# Sheet1.net
KiCad netlist of a schematic drawn in Altium Designer
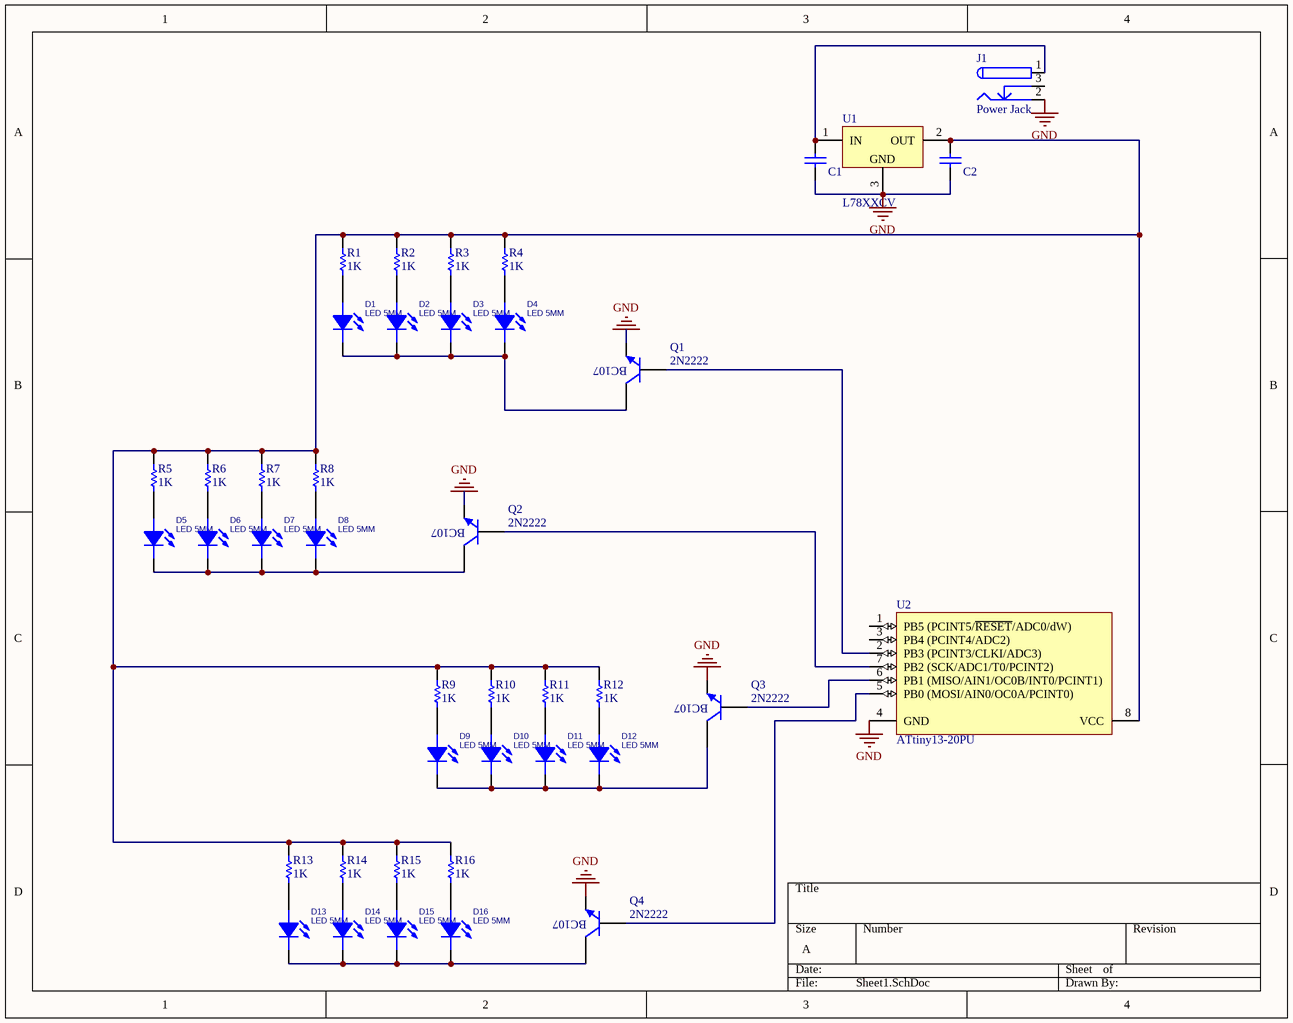
[diagram p0: Sheet1.SchDoc]

(export (version "E")
  (design (tool "Eeschema 10.0.6"))
  (components
    (comp (ref "C1")
      (value "~")
      (footprint "CBB22")
      (description "Polypropylene film with epoxy Cap CBB22 105J400V")
      (fields (field (name "MANUFACTURER") "CHINA") (field (name "DESIGNER") "Abbas Basereh"))
      (libsource (lib "Altium") (part "Cap CBB22 105J400V"))
    )
    (comp (ref "C2")
      (value "~")
      (footprint "CBB22")
      (description "Polypropylene film with epoxy Cap CBB22 105J400V")
      (fields (field (name "MANUFACTURER") "CHINA") (field (name "DESIGNER") "Abbas Basereh"))
      (libsource (lib "Altium") (part "Cap CBB22 105J400V"))
    )
    (comp (ref "D1")
      (value "LED 5MM")
      (footprint "LED5MM_BLUE")
      (description "Light Emitting Diode")
      (fields (field (name "DESIGNER") "Abbas Basereh"))
      (libsource (lib "Altium") (part "LED 5MM"))
    )
    (comp (ref "D2")
      (value "LED 5MM")
      (footprint "LED5MM_BLUE")
      (description "Light Emitting Diode")
      (fields (field (name "DESIGNER") "Abbas Basereh"))
      (libsource (lib "Altium") (part "LED 5MM"))
    )
    (comp (ref "D3")
      (value "LED 5MM")
      (footprint "LED5MM_BLUE")
      (description "Light Emitting Diode")
      (fields (field (name "DESIGNER") "Abbas Basereh"))
      (libsource (lib "Altium") (part "LED 5MM"))
    )
    (comp (ref "D4")
      (value "LED 5MM")
      (footprint "LED5MM_BLUE")
      (description "Light Emitting Diode")
      (fields (field (name "DESIGNER") "Abbas Basereh"))
      (libsource (lib "Altium") (part "LED 5MM"))
    )
    (comp (ref "D5")
      (value "LED 5MM")
      (footprint "LED5MM_BLUE")
      (description "Light Emitting Diode")
      (fields (field (name "DESIGNER") "Abbas Basereh"))
      (libsource (lib "Altium") (part "LED 5MM"))
    )
    (comp (ref "D6")
      (value "LED 5MM")
      (footprint "LED5MM_BLUE")
      (description "Light Emitting Diode")
      (fields (field (name "DESIGNER") "Abbas Basereh"))
      (libsource (lib "Altium") (part "LED 5MM"))
    )
    (comp (ref "D7")
      (value "LED 5MM")
      (footprint "LED5MM_BLUE")
      (description "Light Emitting Diode")
      (fields (field (name "DESIGNER") "Abbas Basereh"))
      (libsource (lib "Altium") (part "LED 5MM"))
    )
    (comp (ref "D8")
      (value "LED 5MM")
      (footprint "LED5MM_BLUE")
      (description "Light Emitting Diode")
      (fields (field (name "DESIGNER") "Abbas Basereh"))
      (libsource (lib "Altium") (part "LED 5MM"))
    )
    (comp (ref "D9")
      (value "LED 5MM")
      (footprint "LED5MM_BLUE")
      (description "Light Emitting Diode")
      (fields (field (name "DESIGNER") "Abbas Basereh"))
      (libsource (lib "Altium") (part "LED 5MM"))
    )
    (comp (ref "D10")
      (value "LED 5MM")
      (footprint "LED5MM_BLUE")
      (description "Light Emitting Diode")
      (fields (field (name "DESIGNER") "Abbas Basereh"))
      (libsource (lib "Altium") (part "LED 5MM"))
    )
    (comp (ref "D11")
      (value "LED 5MM")
      (footprint "LED5MM_BLUE")
      (description "Light Emitting Diode")
      (fields (field (name "DESIGNER") "Abbas Basereh"))
      (libsource (lib "Altium") (part "LED 5MM"))
    )
    (comp (ref "D12")
      (value "LED 5MM")
      (footprint "LED5MM_BLUE")
      (description "Light Emitting Diode")
      (fields (field (name "DESIGNER") "Abbas Basereh"))
      (libsource (lib "Altium") (part "LED 5MM"))
    )
    (comp (ref "D13")
      (value "LED 5MM")
      (footprint "LED5MM_BLUE")
      (description "Light Emitting Diode")
      (fields (field (name "DESIGNER") "Abbas Basereh"))
      (libsource (lib "Altium") (part "LED 5MM"))
    )
    (comp (ref "D14")
      (value "LED 5MM")
      (footprint "LED5MM_BLUE")
      (description "Light Emitting Diode")
      (fields (field (name "DESIGNER") "Abbas Basereh"))
      (libsource (lib "Altium") (part "LED 5MM"))
    )
    (comp (ref "D15")
      (value "LED 5MM")
      (footprint "LED5MM_BLUE")
      (description "Light Emitting Diode")
      (fields (field (name "DESIGNER") "Abbas Basereh"))
      (libsource (lib "Altium") (part "LED 5MM"))
    )
    (comp (ref "D16")
      (value "LED 5MM")
      (footprint "LED5MM_BLUE")
      (description "Light Emitting Diode")
      (fields (field (name "DESIGNER") "Abbas Basereh"))
      (libsource (lib "Altium") (part "LED 5MM"))
    )
    (comp (ref "J1")
      (value "Power Jack")
      (footprint "Power Jack")
      (fields (field (name "DESIGNER") "Saeid Jorablo"))
      (libsource (lib "My_Library") (part "Power Jack"))
    )
    (comp (ref "Q1")
      (value "2N2222")
      (footprint "2N2222")
      (description "NPN Transistor")
      (libsource (lib "Altium") (part "2N2222"))
    )
    (comp (ref "Q2")
      (value "2N2222")
      (footprint "2N2222")
      (description "NPN Transistor")
      (libsource (lib "Altium") (part "2N2222"))
    )
    (comp (ref "Q3")
      (value "2N2222")
      (footprint "2N2222")
      (description "NPN Transistor")
      (libsource (lib "Altium") (part "2N2222"))
    )
    (comp (ref "Q4")
      (value "2N2222")
      (footprint "2N2222")
      (description "NPN Transistor")
      (libsource (lib "Altium") (part "2N2222"))
    )
    (comp (ref "R1")
      (value "1K")
      (footprint "RES-(1/1)")
      (description "TOTAL DIP RESISTOR PACK")
      (fields (field (name "DESIGNER") "Ali Hafizi"))
      (libsource (lib "Altium") (part "RES DIP PACKAGE"))
    )
    (comp (ref "R2")
      (value "1K")
      (footprint "RES-(1/1)")
      (description "TOTAL DIP RESISTOR PACK")
      (fields (field (name "DESIGNER") "Ali Hafizi"))
      (libsource (lib "Altium") (part "RES DIP PACKAGE"))
    )
    (comp (ref "R3")
      (value "1K")
      (footprint "RES-(1/1)")
      (description "TOTAL DIP RESISTOR PACK")
      (fields (field (name "DESIGNER") "Ali Hafizi"))
      (libsource (lib "Altium") (part "RES DIP PACKAGE"))
    )
    (comp (ref "R4")
      (value "1K")
      (footprint "RES-(1/1)")
      (description "TOTAL DIP RESISTOR PACK")
      (fields (field (name "DESIGNER") "Ali Hafizi"))
      (libsource (lib "Altium") (part "RES DIP PACKAGE"))
    )
    (comp (ref "R5")
      (value "1K")
      (footprint "RES-(1/1)")
      (description "TOTAL DIP RESISTOR PACK")
      (fields (field (name "DESIGNER") "Ali Hafizi"))
      (libsource (lib "Altium") (part "RES DIP PACKAGE"))
    )
    (comp (ref "R6")
      (value "1K")
      (footprint "RES-(1/1)")
      (description "TOTAL DIP RESISTOR PACK")
      (fields (field (name "DESIGNER") "Ali Hafizi"))
      (libsource (lib "Altium") (part "RES DIP PACKAGE"))
    )
    (comp (ref "R7")
      (value "1K")
      (footprint "RES-(1/1)")
      (description "TOTAL DIP RESISTOR PACK")
      (fields (field (name "DESIGNER") "Ali Hafizi"))
      (libsource (lib "Altium") (part "RES DIP PACKAGE"))
    )
    (comp (ref "R8")
      (value "1K")
      (footprint "RES-(1/1)")
      (description "TOTAL DIP RESISTOR PACK")
      (fields (field (name "DESIGNER") "Ali Hafizi"))
      (libsource (lib "Altium") (part "RES DIP PACKAGE"))
    )
    (comp (ref "R9")
      (value "1K")
      (footprint "RES-(1/1)")
      (description "TOTAL DIP RESISTOR PACK")
      (fields (field (name "DESIGNER") "Ali Hafizi"))
      (libsource (lib "Altium") (part "RES DIP PACKAGE"))
    )
    (comp (ref "R10")
      (value "1K")
      (footprint "RES-(1/1)")
      (description "TOTAL DIP RESISTOR PACK")
      (fields (field (name "DESIGNER") "Ali Hafizi"))
      (libsource (lib "Altium") (part "RES DIP PACKAGE"))
    )
    (comp (ref "R11")
      (value "1K")
      (footprint "RES-(1/1)")
      (description "TOTAL DIP RESISTOR PACK")
      (fields (field (name "DESIGNER") "Ali Hafizi"))
      (libsource (lib "Altium") (part "RES DIP PACKAGE"))
    )
    (comp (ref "R12")
      (value "1K")
      (footprint "RES-(1/1)")
      (description "TOTAL DIP RESISTOR PACK")
      (fields (field (name "DESIGNER") "Ali Hafizi"))
      (libsource (lib "Altium") (part "RES DIP PACKAGE"))
    )
    (comp (ref "R13")
      (value "1K")
      (footprint "RES-(1/1)")
      (description "TOTAL DIP RESISTOR PACK")
      (fields (field (name "DESIGNER") "Ali Hafizi"))
      (libsource (lib "Altium") (part "RES DIP PACKAGE"))
    )
    (comp (ref "R14")
      (value "1K")
      (footprint "RES-(1/1)")
      (description "TOTAL DIP RESISTOR PACK")
      (fields (field (name "DESIGNER") "Ali Hafizi"))
      (libsource (lib "Altium") (part "RES DIP PACKAGE"))
    )
    (comp (ref "R15")
      (value "1K")
      (footprint "RES-(1/1)")
      (description "TOTAL DIP RESISTOR PACK")
      (fields (field (name "DESIGNER") "Ali Hafizi"))
      (libsource (lib "Altium") (part "RES DIP PACKAGE"))
    )
    (comp (ref "R16")
      (value "1K")
      (footprint "RES-(1/1)")
      (description "TOTAL DIP RESISTOR PACK")
      (fields (field (name "DESIGNER") "Ali Hafizi"))
      (libsource (lib "Altium") (part "RES DIP PACKAGE"))
    )
    (comp (ref "U1")
      (value "L78XXCV")
      (footprint "78XXCV - Right")
      (description "Fixed Voltage Regulator")
      (fields (field (name "DESIGNER") "Saeid Jorablo"))
      (libsource (lib "Altium") (part "L78XXCV"))
    )
    (comp (ref "U2")
      (value "ATtiny13-20PU")
      (footprint "8P3")
      (fields (field (name "PUBLISHER") "Abbas Basereh"))
      (libsource (lib "Altium") (part "ATtiny13-20PU"))
    )
  )
  (nets
    (net (code "1") (name "GND") (class "Default")
      (node (ref "C1") (pin "1") (pinfunction "1_1") (pintype "passive"))
      (node (ref "C2") (pin "1") (pinfunction "1_1") (pintype "passive"))
      (node (ref "J1") (pin "2") (pinfunction "2_2") (pintype "power_in"))
      (node (ref "Q1") (pin "1") (pinfunction "E_1") (pintype "passive"))
      (node (ref "Q2") (pin "1") (pinfunction "E_1") (pintype "passive"))
      (node (ref "U1") (pin "3") (pinfunction "GND_3") (pintype "passive"))
      (node (ref "U2") (pin "4") (pinfunction "GND_4") (pintype "power_in"))
    )
    (net (code "2") (name "Net-(D1-ANODE)") (class "Default")
      (node (ref "D1") (pin "1") (pinfunction "ANODE_1") (pintype "passive"))
      (node (ref "R1") (pin "1") (pinfunction "1_1") (pintype "passive"))
    )
    (net (code "3") (name "Net-(D1-CATHODE)") (class "Default")
      (node (ref "D1") (pin "2") (pinfunction "CATHODE_2") (pintype "passive"))
      (node (ref "D2") (pin "2") (pinfunction "CATHODE_2") (pintype "passive"))
      (node (ref "D3") (pin "2") (pinfunction "CATHODE_2") (pintype "passive"))
      (node (ref "D4") (pin "2") (pinfunction "CATHODE_2") (pintype "passive"))
      (node (ref "Q1") (pin "3") (pinfunction "C_3") (pintype "passive"))
    )
    (net (code "4") (name "Net-(D2-ANODE)") (class "Default")
      (node (ref "D2") (pin "1") (pinfunction "ANODE_1") (pintype "passive"))
      (node (ref "R2") (pin "1") (pinfunction "1_1") (pintype "passive"))
    )
    (net (code "5") (name "Net-(D3-ANODE)") (class "Default")
      (node (ref "D3") (pin "1") (pinfunction "ANODE_1") (pintype "passive"))
      (node (ref "R3") (pin "1") (pinfunction "1_1") (pintype "passive"))
    )
    (net (code "6") (name "Net-(D4-ANODE)") (class "Default")
      (node (ref "D4") (pin "1") (pinfunction "ANODE_1") (pintype "passive"))
      (node (ref "R4") (pin "1") (pinfunction "1_1") (pintype "passive"))
    )
    (net (code "7") (name "Net-(D5-ANODE)") (class "Default")
      (node (ref "D5") (pin "1") (pinfunction "ANODE_1") (pintype "passive"))
      (node (ref "R5") (pin "1") (pinfunction "1_1") (pintype "passive"))
    )
    (net (code "8") (name "Net-(D5-CATHODE)") (class "Default")
      (node (ref "D5") (pin "2") (pinfunction "CATHODE_2") (pintype "passive"))
      (node (ref "D6") (pin "2") (pinfunction "CATHODE_2") (pintype "passive"))
      (node (ref "D7") (pin "2") (pinfunction "CATHODE_2") (pintype "passive"))
      (node (ref "D8") (pin "2") (pinfunction "CATHODE_2") (pintype "passive"))
      (node (ref "Q2") (pin "3") (pinfunction "C_3") (pintype "passive"))
    )
    (net (code "9") (name "Net-(D6-ANODE)") (class "Default")
      (node (ref "D6") (pin "1") (pinfunction "ANODE_1") (pintype "passive"))
      (node (ref "R6") (pin "1") (pinfunction "1_1") (pintype "passive"))
    )
    (net (code "10") (name "Net-(D7-ANODE)") (class "Default")
      (node (ref "D7") (pin "1") (pinfunction "ANODE_1") (pintype "passive"))
      (node (ref "R7") (pin "1") (pinfunction "1_1") (pintype "passive"))
    )
    (net (code "11") (name "Net-(D8-ANODE)") (class "Default")
      (node (ref "D8") (pin "1") (pinfunction "ANODE_1") (pintype "passive"))
      (node (ref "R8") (pin "1") (pinfunction "1_1") (pintype "passive"))
    )
    (net (code "12") (name "Net-(D9-ANODE)") (class "Default")
      (node (ref "D9") (pin "1") (pinfunction "ANODE_1") (pintype "passive"))
      (node (ref "R9") (pin "1") (pinfunction "1_1") (pintype "passive"))
    )
    (net (code "13") (name "Net-(D10-ANODE)") (class "Default")
      (node (ref "D10") (pin "1") (pinfunction "ANODE_1") (pintype "passive"))
      (node (ref "R10") (pin "1") (pinfunction "1_1") (pintype "passive"))
    )
    (net (code "14") (name "Net-(D10-CATHODE)") (class "Default")
      (node (ref "D10") (pin "2") (pinfunction "CATHODE_2") (pintype "passive"))
      (node (ref "D11") (pin "2") (pinfunction "CATHODE_2") (pintype "passive"))
      (node (ref "D12") (pin "2") (pinfunction "CATHODE_2") (pintype "passive"))
      (node (ref "D9") (pin "2") (pinfunction "CATHODE_2") (pintype "passive"))
      (node (ref "Q3") (pin "3") (pinfunction "C_3") (pintype "passive"))
    )
    (net (code "15") (name "Net-(D11-ANODE)") (class "Default")
      (node (ref "D11") (pin "1") (pinfunction "ANODE_1") (pintype "passive"))
      (node (ref "R11") (pin "1") (pinfunction "1_1") (pintype "passive"))
    )
    (net (code "16") (name "Net-(D12-ANODE)") (class "Default")
      (node (ref "D12") (pin "1") (pinfunction "ANODE_1") (pintype "passive"))
      (node (ref "R12") (pin "1") (pinfunction "1_1") (pintype "passive"))
    )
    (net (code "17") (name "Net-(D13-ANODE)") (class "Default")
      (node (ref "D13") (pin "1") (pinfunction "ANODE_1") (pintype "passive"))
      (node (ref "R13") (pin "1") (pinfunction "1_1") (pintype "passive"))
    )
    (net (code "18") (name "Net-(D13-CATHODE)") (class "Default")
      (node (ref "D13") (pin "2") (pinfunction "CATHODE_2") (pintype "passive"))
      (node (ref "D14") (pin "2") (pinfunction "CATHODE_2") (pintype "passive"))
      (node (ref "D15") (pin "2") (pinfunction "CATHODE_2") (pintype "passive"))
      (node (ref "D16") (pin "2") (pinfunction "CATHODE_2") (pintype "passive"))
      (node (ref "Q4") (pin "3") (pinfunction "C_3") (pintype "passive"))
    )
    (net (code "19") (name "Net-(D14-ANODE)") (class "Default")
      (node (ref "D14") (pin "1") (pinfunction "ANODE_1") (pintype "passive"))
      (node (ref "R14") (pin "1") (pinfunction "1_1") (pintype "passive"))
    )
    (net (code "20") (name "Net-(D15-ANODE)") (class "Default")
      (node (ref "D15") (pin "1") (pinfunction "ANODE_1") (pintype "passive"))
      (node (ref "R15") (pin "1") (pinfunction "1_1") (pintype "passive"))
    )
    (net (code "21") (name "Net-(D16-ANODE)") (class "Default")
      (node (ref "D16") (pin "1") (pinfunction "ANODE_1") (pintype "passive"))
      (node (ref "R16") (pin "1") (pinfunction "1_1") (pintype "passive"))
    )
    (net (code "22") (name "Net-(Q1-B)") (class "Default")
      (node (ref "Q1") (pin "2") (pinfunction "B_2") (pintype "passive"))
      (node (ref "U2") (pin "2") (pinfunction "PB3_(PCINT3/CLKI/ADC3)_2") (pintype "bidirectional"))
    )
    (net (code "23") (name "Net-(Q2-B)") (class "Default")
      (node (ref "Q2") (pin "2") (pinfunction "B_2") (pintype "passive"))
      (node (ref "U2") (pin "7") (pinfunction "PB2_(SCK/ADC1/T0/PCINT2)_7") (pintype "bidirectional"))
    )
    (net (code "24") (name "Net-(Q3-B)") (class "Default")
      (node (ref "Q3") (pin "2") (pinfunction "B_2") (pintype "passive"))
      (node (ref "U2") (pin "6") (pinfunction "PB1_(MISO/AIN1/OC0B/INT0/PCINT1)_6") (pintype "bidirectional"))
    )
    (net (code "25") (name "Net-(Q4-B)") (class "Default")
      (node (ref "Q4") (pin "2") (pinfunction "B_2") (pintype "passive"))
      (node (ref "U2") (pin "5") (pinfunction "PB0_(MOSI/AIN0/OC0A/PCINT0)_5") (pintype "bidirectional"))
    )
    (net (code "26") (name "Net-(U1-IN)") (class "Default")
      (node (ref "C1") (pin "2") (pinfunction "2_2") (pintype "passive"))
      (node (ref "J1") (pin "1") (pinfunction "1_1") (pintype "power_in"))
      (node (ref "U1") (pin "1") (pinfunction "IN_1") (pintype "passive"))
    )
    (net (code "27") (name "Net-(U1-OUT)") (class "Default")
      (node (ref "C2") (pin "2") (pinfunction "2_2") (pintype "passive"))
      (node (ref "R1") (pin "2") (pinfunction "2_2") (pintype "passive"))
      (node (ref "R10") (pin "2") (pinfunction "2_2") (pintype "passive"))
      (node (ref "R11") (pin "2") (pinfunction "2_2") (pintype "passive"))
      (node (ref "R12") (pin "2") (pinfunction "2_2") (pintype "passive"))
      (node (ref "R13") (pin "2") (pinfunction "2_2") (pintype "passive"))
      (node (ref "R14") (pin "2") (pinfunction "2_2") (pintype "passive"))
      (node (ref "R15") (pin "2") (pinfunction "2_2") (pintype "passive"))
      (node (ref "R16") (pin "2") (pinfunction "2_2") (pintype "passive"))
      (node (ref "R2") (pin "2") (pinfunction "2_2") (pintype "passive"))
      (node (ref "R3") (pin "2") (pinfunction "2_2") (pintype "passive"))
      (node (ref "R4") (pin "2") (pinfunction "2_2") (pintype "passive"))
      (node (ref "R5") (pin "2") (pinfunction "2_2") (pintype "passive"))
      (node (ref "R6") (pin "2") (pinfunction "2_2") (pintype "passive"))
      (node (ref "R7") (pin "2") (pinfunction "2_2") (pintype "passive"))
      (node (ref "R8") (pin "2") (pinfunction "2_2") (pintype "passive"))
      (node (ref "R9") (pin "2") (pinfunction "2_2") (pintype "passive"))
      (node (ref "U1") (pin "2") (pinfunction "OUT_2") (pintype "passive"))
      (node (ref "U2") (pin "8") (pinfunction "VCC_8") (pintype "power_in"))
    )
    (net (code "28") (name "unconnected-(J1-Pad3)") (class "Default")
      (node (ref "J1") (pin "3") (pinfunction "3_3") (pintype "power_in"))
    )
    (net (code "29") (name "unconnected-(Q3-E-Pad1)") (class "Default")
      (node (ref "Q3") (pin "1") (pinfunction "E_1") (pintype "passive"))
    )
    (net (code "30") (name "unconnected-(Q4-E-Pad1)") (class "Default")
      (node (ref "Q4") (pin "1") (pinfunction "E_1") (pintype "passive"))
    )
    (net (code "31") (name "unconnected-(U2-PB4_(PCINT4{slash}ADC2)-Pad3)") (class "Default")
      (node (ref "U2") (pin "3") (pinfunction "PB4_(PCINT4/ADC2)_3") (pintype "bidirectional"))
    )
    (net (code "32") (name "unconnected-(U2-PB5_(PCINT5{slash}~{RESET}{slash}ADC0{slash}dW)-Pad1)") (class "Default")
      (node (ref "U2") (pin "1") (pinfunction "PB5_(PCINT5/~{RESET}/ADC0/dW)_1") (pintype "bidirectional"))
    )
  )
)
